# THAT1512_INA128_input_NEVIN_v4.net
KiCad netlist of a schematic drawn in EAGLE
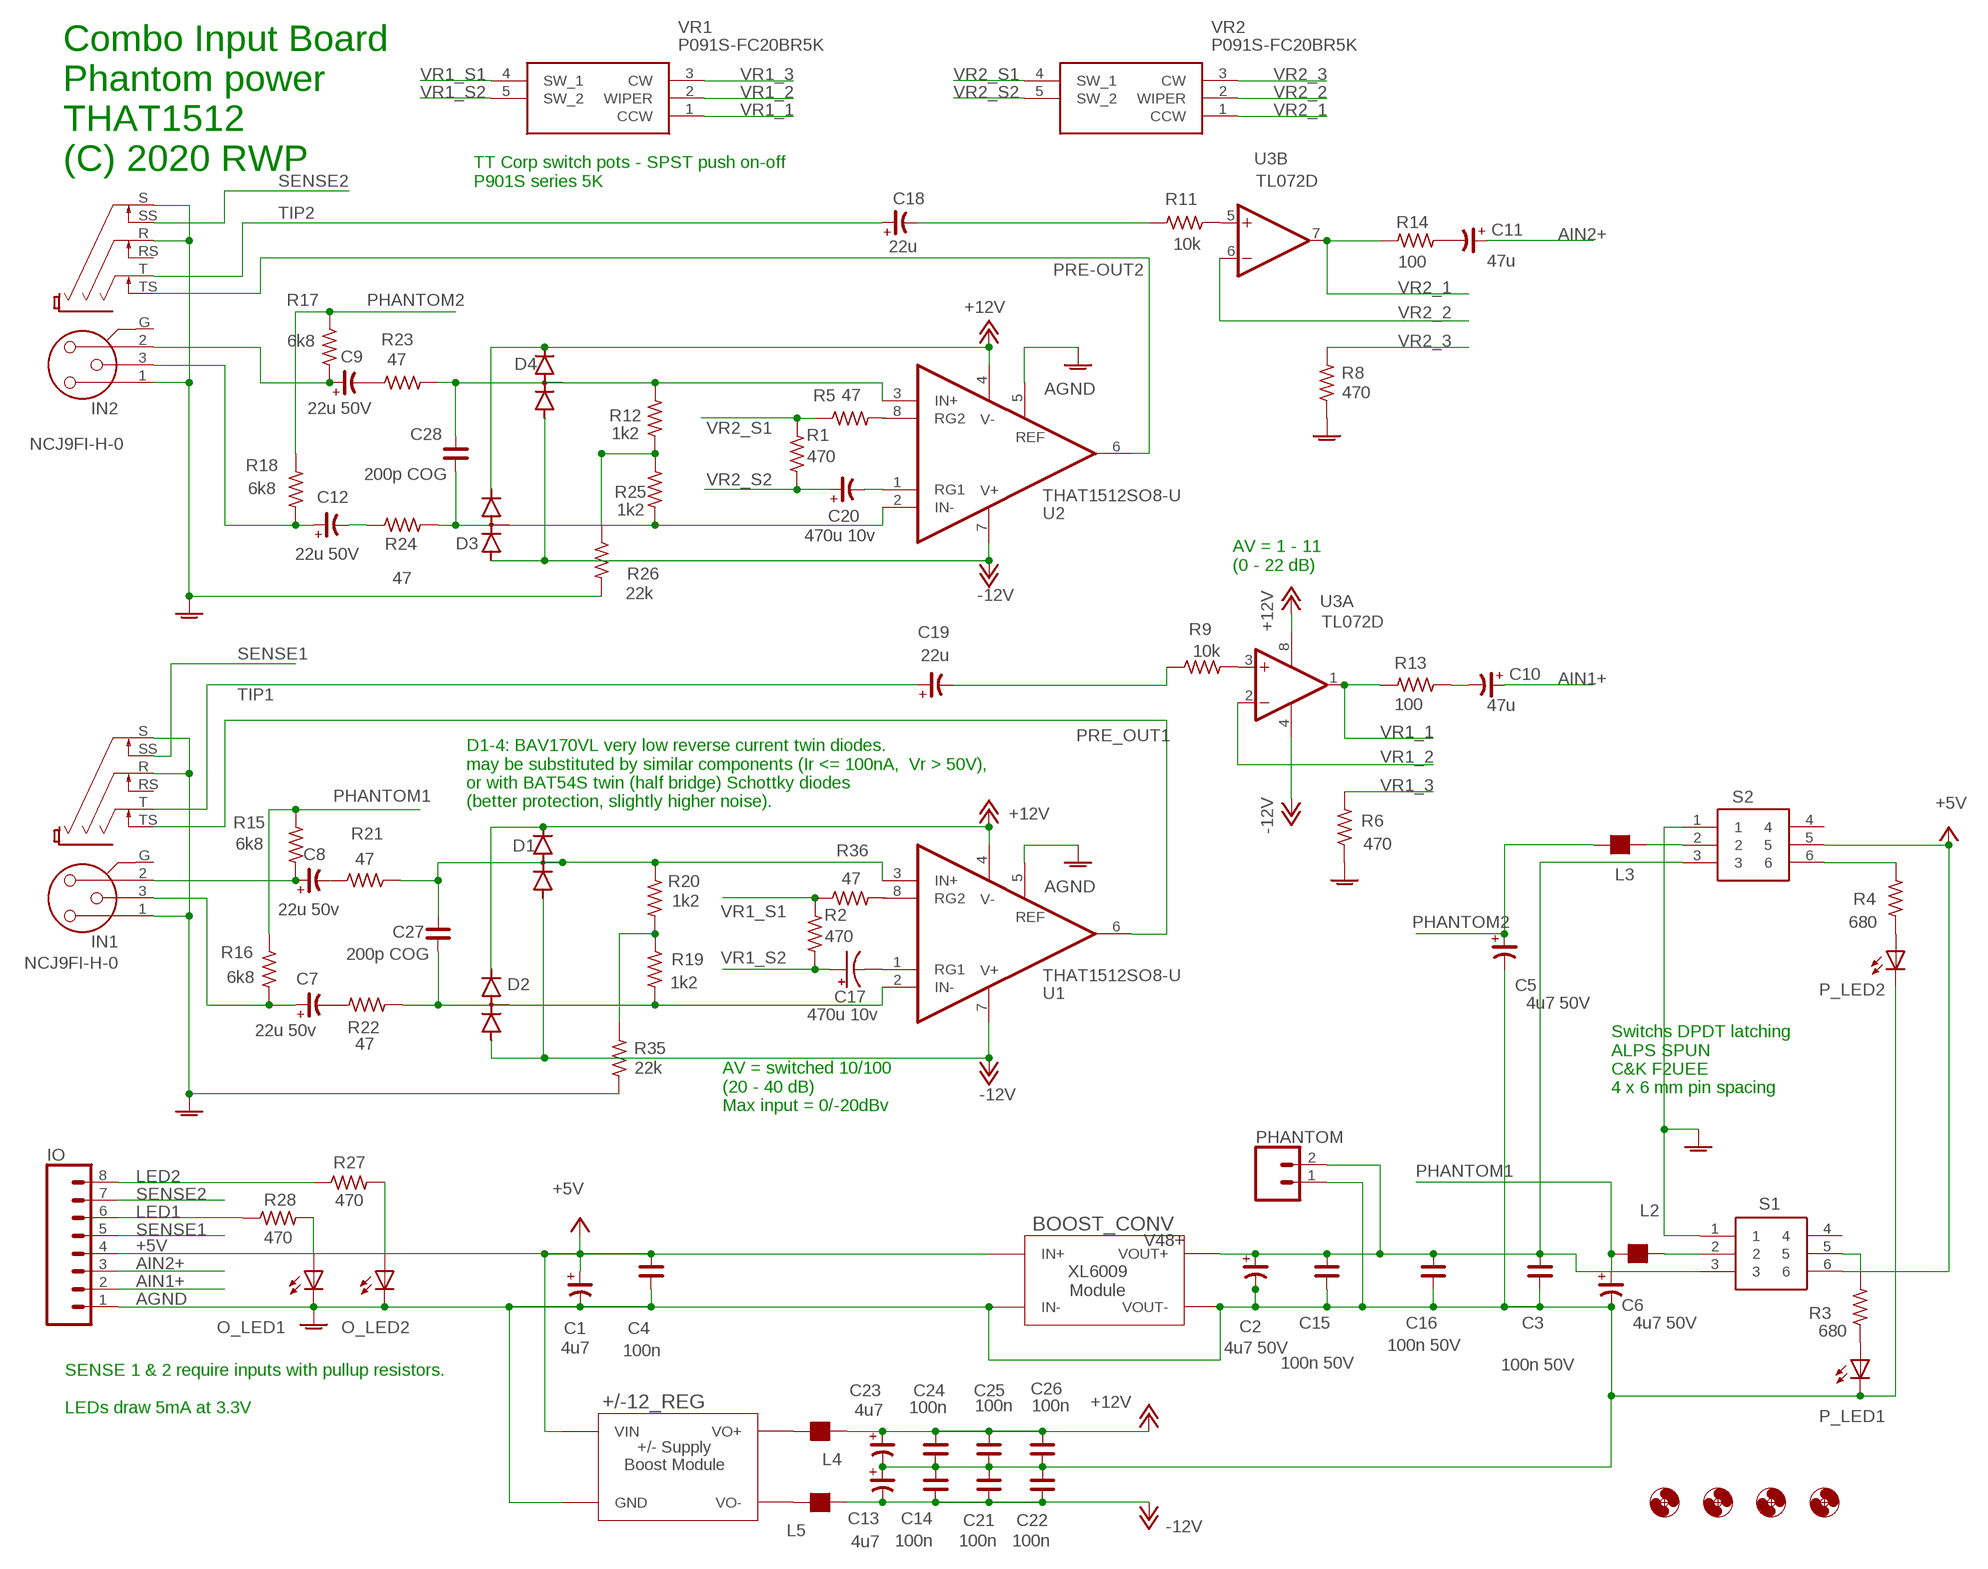
[diagram p0: schematic, sheet 1]

(export (version "E")
  (design (tool "Eeschema 10.0.6"))
  (components
    (comp (ref "+/-12_REG")
      (value "POS_NEG_SUP_MODULE")
      (footprint "eagle-import:POS_NEG_SUP_MODULE_F")
      (libsource (lib "eagle-import") (part "POS_NEG_SUP_MODULE"))
    )
    (comp (ref "BOOST_CONV")
      (value "XL6009_MODULE")
      (footprint "eagle-import:XL6009_MODULE_F")
      (libsource (lib "eagle-import") (part "XL6009_MODULE"))
    )
    (comp (ref "C1")
      (value "4u7")
      (footprint "eagle-import:C3216_T")
      (libsource (lib "eagle-import") (part "CP_3216"))
    )
    (comp (ref "C2")
      (value "4u7 50V")
      (footprint "eagle-import:C3216_T")
      (libsource (lib "eagle-import") (part "CP_3216"))
    )
    (comp (ref "C3")
      (value "100n 50V")
      (footprint "eagle-import:C0805")
      (libsource (lib "eagle-import") (part "C_0805"))
    )
    (comp (ref "C4")
      (value "100n")
      (footprint "eagle-import:C0805")
      (libsource (lib "eagle-import") (part "C_0805"))
    )
    (comp (ref "C5")
      (value "4u7 50V")
      (footprint "eagle-import:C3216_T")
      (libsource (lib "eagle-import") (part "CP_3216"))
    )
    (comp (ref "C6")
      (value "4u7 50V")
      (footprint "eagle-import:C3216_T")
      (libsource (lib "eagle-import") (part "CP_3216"))
    )
    (comp (ref "C7")
      (value "22u 50v")
      (footprint "eagle-import:CSV-C")
      (libsource (lib "eagle-import") (part "CP_SV-C"))
    )
    (comp (ref "C8")
      (value "22u 50v")
      (footprint "eagle-import:CSV-C")
      (libsource (lib "eagle-import") (part "CP_SV-C"))
    )
    (comp (ref "C9")
      (value "22u 50V")
      (footprint "eagle-import:CSV-C")
      (libsource (lib "eagle-import") (part "CP_SV-C"))
    )
    (comp (ref "C10")
      (value "47u")
      (footprint "eagle-import:CSV-B")
      (libsource (lib "eagle-import") (part "CP_SV-B"))
    )
    (comp (ref "C11")
      (value "47u")
      (footprint "eagle-import:CSV-B")
      (libsource (lib "eagle-import") (part "CP_SV-B"))
    )
    (comp (ref "C12")
      (value "22u 50V")
      (footprint "eagle-import:CSV-C")
      (libsource (lib "eagle-import") (part "CP_SV-C"))
    )
    (comp (ref "C13")
      (value "4u7")
      (footprint "eagle-import:C3216_T")
      (libsource (lib "eagle-import") (part "CP_3216"))
    )
    (comp (ref "C14")
      (value "100n")
      (footprint "eagle-import:C0805")
      (libsource (lib "eagle-import") (part "C_0805"))
    )
    (comp (ref "C15")
      (value "100n 50V")
      (footprint "eagle-import:C0805")
      (libsource (lib "eagle-import") (part "C_0805"))
    )
    (comp (ref "C16")
      (value "100n 50V")
      (footprint "eagle-import:C0805")
      (libsource (lib "eagle-import") (part "C_0805"))
    )
    (comp (ref "C17")
      (value "470u 10v")
      (footprint "eagle-import:153CLV-0605")
      (libsource (lib "eagle-import") (part "CPOL-US153CLV-0605"))
    )
    (comp (ref "C18")
      (value "22u")
      (footprint "eagle-import:CSV-B")
      (libsource (lib "eagle-import") (part "CP_SV-B"))
    )
    (comp (ref "C19")
      (value "22u")
      (footprint "eagle-import:CSV-B")
      (libsource (lib "eagle-import") (part "CP_SV-B"))
    )
    (comp (ref "C20")
      (value "470u 10v")
      (footprint "eagle-import:CSV-C")
      (libsource (lib "eagle-import") (part "CP_SV-C"))
    )
    (comp (ref "C21")
      (value "100n")
      (footprint "eagle-import:C0805")
      (libsource (lib "eagle-import") (part "C_0805"))
    )
    (comp (ref "C22")
      (value "100n")
      (footprint "eagle-import:C0805")
      (libsource (lib "eagle-import") (part "C_0805"))
    )
    (comp (ref "C23")
      (value "4u7")
      (footprint "eagle-import:C3216_T")
      (libsource (lib "eagle-import") (part "CP_3216"))
    )
    (comp (ref "C24")
      (value "100n")
      (footprint "eagle-import:C0805")
      (libsource (lib "eagle-import") (part "C_0805"))
    )
    (comp (ref "C25")
      (value "100n")
      (footprint "eagle-import:C0805")
      (libsource (lib "eagle-import") (part "C_0805"))
    )
    (comp (ref "C26")
      (value "100n")
      (footprint "eagle-import:C0805")
      (libsource (lib "eagle-import") (part "C_0805"))
    )
    (comp (ref "C27")
      (value "200p COG")
      (footprint "eagle-import:C0805")
      (libsource (lib "eagle-import") (part "C_0805"))
    )
    (comp (ref "C28")
      (value "200p COG")
      (footprint "eagle-import:C0805")
      (libsource (lib "eagle-import") (part "C_0805"))
    )
    (comp (ref "D1")
      (value "HSMS-285C")
      (footprint "eagle-import:SOT323")
      (libsource (lib "eagle-import") (part "HSMS-285C"))
    )
    (comp (ref "D2")
      (value "HSMS-285C")
      (footprint "eagle-import:SOT323")
      (libsource (lib "eagle-import") (part "HSMS-285C"))
    )
    (comp (ref "D3")
      (value "HSMS-285C")
      (footprint "eagle-import:SOT323")
      (libsource (lib "eagle-import") (part "HSMS-285C"))
    )
    (comp (ref "D4")
      (value "HSMS-285C")
      (footprint "eagle-import:SOT323")
      (libsource (lib "eagle-import") (part "HSMS-285C"))
    )
    (comp (ref "H1")
      (value "MOUNT-HOLE3.6")
      (footprint "eagle-import:3,6")
      (libsource (lib "eagle-import") (part "MOUNT-HOLE3.6"))
    )
    (comp (ref "H2")
      (value "MOUNT-HOLE3.6")
      (footprint "eagle-import:3,6")
      (libsource (lib "eagle-import") (part "MOUNT-HOLE3.6"))
    )
    (comp (ref "H3")
      (value "MOUNT-HOLE3.6")
      (footprint "eagle-import:3,6")
      (libsource (lib "eagle-import") (part "MOUNT-HOLE3.6"))
    )
    (comp (ref "H4")
      (value "MOUNT-HOLE3.6")
      (footprint "eagle-import:3,6")
      (libsource (lib "eagle-import") (part "MOUNT-HOLE3.6"))
    )
    (comp (ref "IN1")
      (value "NCJ9FI-H-0")
      (footprint "eagle-import:NCJ9FI-H")
      (libsource (lib "eagle-import") (part "NCJ9FI-H-0"))
    )
    (comp (ref "IN2")
      (value "NCJ9FI-H-0")
      (footprint "eagle-import:NCJ9FI-H")
      (libsource (lib "eagle-import") (part "NCJ9FI-H-0"))
    )
    (comp (ref "IO")
      (value "CONN_08\"")
      (footprint "eagle-import:1X08")
      (libsource (lib "eagle-import") (part "CONN_08{dblquote}"))
    )
    (comp (ref "L2")
      (value "150")
      (footprint "eagle-import:L0805")
      (libsource (lib "eagle-import") (part "FB_0805"))
    )
    (comp (ref "L3")
      (value "150")
      (footprint "eagle-import:L0805")
      (libsource (lib "eagle-import") (part "FB_0805"))
    )
    (comp (ref "L4")
      (value "150")
      (footprint "eagle-import:L0805")
      (libsource (lib "eagle-import") (part "FB_0805"))
    )
    (comp (ref "L5")
      (value "150")
      (footprint "eagle-import:L0805")
      (libsource (lib "eagle-import") (part "FB_0805"))
    )
    (comp (ref "O_LED1")
      (value "LED3MM")
      (footprint "eagle-import:LED3MM")
      (libsource (lib "eagle-import") (part "LED3MM"))
    )
    (comp (ref "O_LED2")
      (value "LED3MM")
      (footprint "eagle-import:LED3MM")
      (libsource (lib "eagle-import") (part "LED3MM"))
    )
    (comp (ref "PHANTOM")
      (value "CONN_02")
      (footprint "eagle-import:1X02")
      (libsource (lib "eagle-import") (part "CONN_02"))
    )
    (comp (ref "P_LED1")
      (value "LED3MM")
      (footprint "eagle-import:LED3MM")
      (libsource (lib "eagle-import") (part "LED3MM"))
    )
    (comp (ref "P_LED2")
      (value "LED3MM")
      (footprint "eagle-import:LED3MM")
      (libsource (lib "eagle-import") (part "LED3MM"))
    )
    (comp (ref "R1")
      (value "470")
      (footprint "eagle-import:R0805")
      (libsource (lib "eagle-import") (part "R_0805"))
    )
    (comp (ref "R2")
      (value "470")
      (footprint "eagle-import:R0805")
      (libsource (lib "eagle-import") (part "R_0805"))
    )
    (comp (ref "R3")
      (value "680")
      (footprint "eagle-import:R0805")
      (libsource (lib "eagle-import") (part "R_0805"))
    )
    (comp (ref "R4")
      (value "680")
      (footprint "eagle-import:R0805")
      (libsource (lib "eagle-import") (part "R_0805"))
    )
    (comp (ref "R5")
      (value "47")
      (footprint "eagle-import:R0805")
      (libsource (lib "eagle-import") (part "R_0805"))
    )
    (comp (ref "R6")
      (value "470")
      (footprint "eagle-import:R0805")
      (libsource (lib "eagle-import") (part "R_0805"))
    )
    (comp (ref "R8")
      (value "470")
      (footprint "eagle-import:R0805")
      (libsource (lib "eagle-import") (part "R_0805"))
    )
    (comp (ref "R9")
      (value "10k")
      (footprint "eagle-import:R0805")
      (libsource (lib "eagle-import") (part "R_0805"))
    )
    (comp (ref "R11")
      (value "10k")
      (footprint "eagle-import:R0805")
      (libsource (lib "eagle-import") (part "R_0805"))
    )
    (comp (ref "R12")
      (value "1k2")
      (footprint "eagle-import:R0805")
      (libsource (lib "eagle-import") (part "R_0805"))
    )
    (comp (ref "R13")
      (value "100")
      (footprint "eagle-import:R0805")
      (libsource (lib "eagle-import") (part "R_0805"))
    )
    (comp (ref "R14")
      (value "100")
      (footprint "eagle-import:R0805")
      (libsource (lib "eagle-import") (part "R_0805"))
    )
    (comp (ref "R15")
      (value "6k8")
      (footprint "eagle-import:R0805")
      (libsource (lib "eagle-import") (part "R_0805"))
    )
    (comp (ref "R16")
      (value "6k8")
      (footprint "eagle-import:R0805")
      (libsource (lib "eagle-import") (part "R_0805"))
    )
    (comp (ref "R17")
      (value "6k8")
      (footprint "eagle-import:R0805")
      (libsource (lib "eagle-import") (part "R_0805"))
    )
    (comp (ref "R18")
      (value "6k8")
      (footprint "eagle-import:R0805")
      (libsource (lib "eagle-import") (part "R_0805"))
    )
    (comp (ref "R19")
      (value "1k2")
      (footprint "eagle-import:R0805")
      (libsource (lib "eagle-import") (part "R_0805"))
    )
    (comp (ref "R20")
      (value "1k2")
      (footprint "eagle-import:R0805")
      (libsource (lib "eagle-import") (part "R_0805"))
    )
    (comp (ref "R21")
      (value "47")
      (footprint "eagle-import:R0805")
      (libsource (lib "eagle-import") (part "R_0805"))
    )
    (comp (ref "R22")
      (value "47")
      (footprint "eagle-import:R0805")
      (libsource (lib "eagle-import") (part "R_0805"))
    )
    (comp (ref "R23")
      (value "47")
      (footprint "eagle-import:R0805")
      (libsource (lib "eagle-import") (part "R_0805"))
    )
    (comp (ref "R24")
      (value "47")
      (footprint "eagle-import:R0805")
      (libsource (lib "eagle-import") (part "R_0805"))
    )
    (comp (ref "R25")
      (value "1k2")
      (footprint "eagle-import:R0805")
      (libsource (lib "eagle-import") (part "R_0805"))
    )
    (comp (ref "R26")
      (value "22k")
      (footprint "eagle-import:R0805")
      (libsource (lib "eagle-import") (part "R_0805"))
    )
    (comp (ref "R27")
      (value "470")
      (footprint "eagle-import:R0805")
      (libsource (lib "eagle-import") (part "R_0805"))
    )
    (comp (ref "R28")
      (value "470")
      (footprint "eagle-import:R0805")
      (libsource (lib "eagle-import") (part "R_0805"))
    )
    (comp (ref "R35")
      (value "22k")
      (footprint "eagle-import:R0805")
      (libsource (lib "eagle-import") (part "R_0805"))
    )
    (comp (ref "R36")
      (value "47")
      (footprint "eagle-import:R0805")
      (libsource (lib "eagle-import") (part "R_0805"))
    )
    (comp (ref "S1")
      (value "SPUN191600")
      (footprint "eagle-import:SPUN191000")
      (fields (field (name "MOUSER_PART_NUMBER") "688-SPUN191600"))
      (libsource (lib "eagle-import") (part "SPUN191600"))
    )
    (comp (ref "S2")
      (value "SPUN191600")
      (footprint "eagle-import:SPUN191000")
      (fields (field (name "MOUSER_PART_NUMBER") "688-SPUN191600"))
      (libsource (lib "eagle-import") (part "SPUN191600"))
    )
    (comp (ref "U1")
      (value "THAT1512SO8-U")
      (footprint "eagle-import:SO08")
      (libsource (lib "eagle-import") (part "THAT1512SO8-U"))
    )
    (comp (ref "U2")
      (value "THAT1512SO8-U")
      (footprint "eagle-import:SO08")
      (libsource (lib "eagle-import") (part "THAT1512SO8-U"))
    )
    (comp (ref "U3")
      (value "TL072D")
      (footprint "eagle-import:SO08")
      (libsource (lib "eagle-import") (part "TL072D"))
    )
    (comp (ref "VR1")
      (value "P091S-FC20BR5K")
      (footprint "eagle-import:P091SFC20BR5K")
      (fields (field (name "MOUSER_PART_NUMBER") "858-P091SFC20BR5K"))
      (libsource (lib "eagle-import") (part "P091S-FC20BR5K"))
    )
    (comp (ref "VR2")
      (value "P091S-FC20BR5K")
      (footprint "eagle-import:P091SFC20BR5K")
      (fields (field (name "MOUSER_PART_NUMBER") "858-P091SFC20BR5K"))
      (libsource (lib "eagle-import") (part "P091S-FC20BR5K"))
    )
  )
  (nets
    (net (code "1") (name "+5V") (class "Default")
      (node (ref "+/-12_REG") (pin "IN+") (pinfunction "VIN_IN+") (pintype "input"))
      (node (ref "BOOST_CONV") (pin "IN+") (pinfunction "IN+_IN+") (pintype "input"))
      (node (ref "C1") (pin "+") (pinfunction "+_+") (pintype "passive"))
      (node (ref "C4") (pin "2") (pinfunction "2_2") (pintype "passive"))
      (node (ref "IO") (pin "4") (pinfunction "4_4") (pintype "passive"))
      (node (ref "S1") (pin "6") (pinfunction "6_6") (pintype "bidirectional"))
      (node (ref "S2") (pin "5") (pinfunction "5_5") (pintype "bidirectional"))
    )
    (net (code "2") (name "+12V") (class "Default")
      (node (ref "C23") (pin "+") (pinfunction "+_+") (pintype "passive"))
      (node (ref "C24") (pin "2") (pinfunction "2_2") (pintype "passive"))
      (node (ref "C25") (pin "2") (pinfunction "2_2") (pintype "passive"))
      (node (ref "C26") (pin "2") (pinfunction "2_2") (pintype "passive"))
      (node (ref "D1") (pin "2") (pinfunction "C_2") (pintype "passive"))
      (node (ref "D2") (pin "2") (pinfunction "C_2") (pintype "passive"))
      (node (ref "D3") (pin "2") (pinfunction "C_2") (pintype "passive"))
      (node (ref "D4") (pin "2") (pinfunction "C_2") (pintype "passive"))
      (node (ref "L4") (pin "1") (pinfunction "1_1") (pintype "passive"))
      (node (ref "U1") (pin "4") (pinfunction "V-_4") (pintype "power_in"))
      (node (ref "U2") (pin "4") (pinfunction "V-_4") (pintype "power_in"))
      (node (ref "U3") (pin "8") (pinfunction "V+_8") (pintype "power_in"))
    )
    (net (code "3") (name "-12V") (class "Default")
      (node (ref "C13") (pin "-") (pinfunction "-_-") (pintype "passive"))
      (node (ref "C14") (pin "1") (pinfunction "1_1") (pintype "passive"))
      (node (ref "C21") (pin "1") (pinfunction "1_1") (pintype "passive"))
      (node (ref "C22") (pin "1") (pinfunction "1_1") (pintype "passive"))
      (node (ref "D1") (pin "1") (pinfunction "A_1") (pintype "passive"))
      (node (ref "D2") (pin "1") (pinfunction "A_1") (pintype "passive"))
      (node (ref "D3") (pin "1") (pinfunction "A_1") (pintype "passive"))
      (node (ref "D4") (pin "1") (pinfunction "A_1") (pintype "passive"))
      (node (ref "L5") (pin "1") (pinfunction "1_1") (pintype "passive"))
      (node (ref "U1") (pin "7") (pinfunction "V+_7") (pintype "power_in"))
      (node (ref "U2") (pin "7") (pinfunction "V+_7") (pintype "power_in"))
      (node (ref "U3") (pin "4") (pinfunction "V-_4") (pintype "power_in"))
    )
    (net (code "4") (name "/AIN1+") (class "Default")
      (node (ref "C10") (pin "+") (pinfunction "+_+") (pintype "passive"))
      (node (ref "IO") (pin "2") (pinfunction "2_2") (pintype "passive"))
    )
    (net (code "5") (name "/AIN2+") (class "Default")
      (node (ref "C11") (pin "+") (pinfunction "+_+") (pintype "passive"))
      (node (ref "IO") (pin "3") (pinfunction "3_3") (pintype "passive"))
    )
    (net (code "6") (name "/LED1") (class "Default")
      (node (ref "IO") (pin "6") (pinfunction "6_6") (pintype "passive"))
      (node (ref "R28") (pin "2") (pinfunction "2_2") (pintype "passive"))
    )
    (net (code "7") (name "/LED2") (class "Default")
      (node (ref "IO") (pin "8") (pinfunction "8_8") (pintype "passive"))
      (node (ref "R27") (pin "2") (pinfunction "2_2") (pintype "passive"))
    )
    (net (code "8") (name "/PHANTOM1") (class "Default")
      (node (ref "C6") (pin "+") (pinfunction "+_+") (pintype "passive"))
      (node (ref "L2") (pin "2") (pinfunction "2_2") (pintype "passive"))
      (node (ref "R15") (pin "2") (pinfunction "2_2") (pintype "passive"))
      (node (ref "R16") (pin "2") (pinfunction "2_2") (pintype "passive"))
    )
    (net (code "9") (name "/PHANTOM2") (class "Default")
      (node (ref "C5") (pin "+") (pinfunction "+_+") (pintype "passive"))
      (node (ref "L3") (pin "2") (pinfunction "2_2") (pintype "passive"))
      (node (ref "R17") (pin "2") (pinfunction "2_2") (pintype "passive"))
      (node (ref "R18") (pin "2") (pinfunction "2_2") (pintype "passive"))
    )
    (net (code "10") (name "/PRE-OUT2") (class "Default")
      (node (ref "IN2") (pin "TS") (pinfunction "TS_TS") (pintype "passive"))
      (node (ref "U2") (pin "6") (pinfunction "OUT_6") (pintype "output"))
    )
    (net (code "11") (name "/PRE_OUT1") (class "Default")
      (node (ref "IN1") (pin "TS") (pinfunction "TS_TS") (pintype "passive"))
      (node (ref "U1") (pin "6") (pinfunction "OUT_6") (pintype "output"))
    )
    (net (code "12") (name "/SENSE1") (class "Default")
      (node (ref "IN1") (pin "SS") (pinfunction "SS_SS") (pintype "passive"))
      (node (ref "IO") (pin "5") (pinfunction "5_5") (pintype "passive"))
    )
    (net (code "13") (name "/SENSE2") (class "Default")
      (node (ref "IN2") (pin "SS") (pinfunction "SS_SS") (pintype "passive"))
      (node (ref "IO") (pin "7") (pinfunction "7_7") (pintype "passive"))
    )
    (net (code "14") (name "/TIP1") (class "Default")
      (node (ref "C19") (pin "+") (pinfunction "+_+") (pintype "passive"))
      (node (ref "IN1") (pin "T") (pinfunction "T_T") (pintype "passive"))
    )
    (net (code "15") (name "/TIP2") (class "Default")
      (node (ref "C18") (pin "+") (pinfunction "+_+") (pintype "passive"))
      (node (ref "IN2") (pin "T") (pinfunction "T_T") (pintype "passive"))
    )
    (net (code "16") (name "/V48+") (class "Default")
      (node (ref "BOOST_CONV") (pin "VOUT+") (pinfunction "VOUT+_VOUT+") (pintype "output"))
      (node (ref "C15") (pin "2") (pinfunction "2_2") (pintype "passive"))
      (node (ref "C16") (pin "2") (pinfunction "2_2") (pintype "passive"))
      (node (ref "C2") (pin "+") (pinfunction "+_+") (pintype "passive"))
      (node (ref "C3") (pin "2") (pinfunction "2_2") (pintype "passive"))
      (node (ref "PHANTOM") (pin "2") (pinfunction "2_2") (pintype "passive"))
      (node (ref "S1") (pin "3") (pinfunction "3_3") (pintype "bidirectional"))
      (node (ref "S2") (pin "3") (pinfunction "3_3") (pintype "bidirectional"))
    )
    (net (code "17") (name "/VR1_1") (class "Default")
      (node (ref "R13") (pin "2") (pinfunction "2_2") (pintype "passive"))
      (node (ref "U3") (pin "1") (pinfunction "OUT_1") (pintype "output"))
      (node (ref "VR1") (pin "1") (pinfunction "CCW_1") (pintype "bidirectional"))
    )
    (net (code "18") (name "/VR1_2") (class "Default")
      (node (ref "U3") (pin "2") (pinfunction "-IN_2") (pintype "input"))
      (node (ref "VR1") (pin "2") (pinfunction "WIPER_2") (pintype "bidirectional"))
    )
    (net (code "19") (name "/VR1_3") (class "Default")
      (node (ref "R6") (pin "1") (pinfunction "1_1") (pintype "passive"))
      (node (ref "VR1") (pin "3") (pinfunction "CW_3") (pintype "bidirectional"))
    )
    (net (code "20") (name "/VR1_S1") (class "Default")
      (node (ref "R2") (pin "1") (pinfunction "1_1") (pintype "passive"))
      (node (ref "R36") (pin "1") (pinfunction "1_1") (pintype "passive"))
      (node (ref "VR1") (pin "4") (pinfunction "SW_1_4") (pintype "bidirectional"))
    )
    (net (code "21") (name "/VR1_S2") (class "Default")
      (node (ref "C17") (pin "+") (pinfunction "+_+") (pintype "passive"))
      (node (ref "R2") (pin "2") (pinfunction "2_2") (pintype "passive"))
      (node (ref "VR1") (pin "5") (pinfunction "SW_2_5") (pintype "bidirectional"))
    )
    (net (code "22") (name "/VR2_1") (class "Default")
      (node (ref "R14") (pin "2") (pinfunction "2_2") (pintype "passive"))
      (node (ref "U3") (pin "7") (pinfunction "OUT_7") (pintype "output"))
      (node (ref "VR2") (pin "1") (pinfunction "CCW_1") (pintype "bidirectional"))
    )
    (net (code "23") (name "/VR2_2") (class "Default")
      (node (ref "U3") (pin "6") (pinfunction "-IN_6") (pintype "input"))
      (node (ref "VR2") (pin "2") (pinfunction "WIPER_2") (pintype "bidirectional"))
    )
    (net (code "24") (name "/VR2_3") (class "Default")
      (node (ref "R8") (pin "1") (pinfunction "1_1") (pintype "passive"))
      (node (ref "VR2") (pin "3") (pinfunction "CW_3") (pintype "bidirectional"))
    )
    (net (code "25") (name "/VR2_S1") (class "Default")
      (node (ref "R1") (pin "1") (pinfunction "1_1") (pintype "passive"))
      (node (ref "R5") (pin "1") (pinfunction "1_1") (pintype "passive"))
      (node (ref "VR2") (pin "4") (pinfunction "SW_1_4") (pintype "bidirectional"))
    )
    (net (code "26") (name "/VR2_S2") (class "Default")
      (node (ref "C20") (pin "+") (pinfunction "+_+") (pintype "passive"))
      (node (ref "R1") (pin "2") (pinfunction "2_2") (pintype "passive"))
      (node (ref "VR2") (pin "5") (pinfunction "SW_2_5") (pintype "bidirectional"))
    )
    (net (code "27") (name "AGND") (class "Default")
      (node (ref "+/-12_REG") (pin "GND") (pinfunction "GND_GND") (pintype "input"))
      (node (ref "+/-12_REG") (pin "GND@1") (pinfunction "GND_GND@1") (pintype "input"))
      (node (ref "BOOST_CONV") (pin "IN-") (pinfunction "IN-_IN-") (pintype "input"))
      (node (ref "BOOST_CONV") (pin "VOUT-") (pinfunction "VOUT-_VOUT-") (pintype "output"))
      (node (ref "C1") (pin "-") (pinfunction "-_-") (pintype "passive"))
      (node (ref "C13") (pin "+") (pinfunction "+_+") (pintype "passive"))
      (node (ref "C14") (pin "2") (pinfunction "2_2") (pintype "passive"))
      (node (ref "C15") (pin "1") (pinfunction "1_1") (pintype "passive"))
      (node (ref "C16") (pin "1") (pinfunction "1_1") (pintype "passive"))
      (node (ref "C2") (pin "-") (pinfunction "-_-") (pintype "passive"))
      (node (ref "C21") (pin "2") (pinfunction "2_2") (pintype "passive"))
      (node (ref "C22") (pin "2") (pinfunction "2_2") (pintype "passive"))
      (node (ref "C23") (pin "-") (pinfunction "-_-") (pintype "passive"))
      (node (ref "C24") (pin "1") (pinfunction "1_1") (pintype "passive"))
      (node (ref "C25") (pin "1") (pinfunction "1_1") (pintype "passive"))
      (node (ref "C26") (pin "1") (pinfunction "1_1") (pintype "passive"))
      (node (ref "C3") (pin "1") (pinfunction "1_1") (pintype "passive"))
      (node (ref "C4") (pin "1") (pinfunction "1_1") (pintype "passive"))
      (node (ref "C5") (pin "-") (pinfunction "-_-") (pintype "passive"))
      (node (ref "C6") (pin "-") (pinfunction "-_-") (pintype "passive"))
      (node (ref "IN1") (pin "1") (pinfunction "1_1") (pintype "passive"))
      (node (ref "IN1") (pin "R") (pinfunction "R_R") (pintype "passive"))
      (node (ref "IN1") (pin "S") (pinfunction "S_S") (pintype "passive"))
      (node (ref "IN2") (pin "1") (pinfunction "1_1") (pintype "passive"))
      (node (ref "IN2") (pin "R") (pinfunction "R_R") (pintype "passive"))
      (node (ref "IN2") (pin "S") (pinfunction "S_S") (pintype "passive"))
      (node (ref "IO") (pin "1") (pinfunction "1_1") (pintype "passive"))
      (node (ref "O_LED1") (pin "K") (pinfunction "C_K") (pintype "passive"))
      (node (ref "O_LED2") (pin "K") (pinfunction "C_K") (pintype "passive"))
      (node (ref "PHANTOM") (pin "1") (pinfunction "1_1") (pintype "passive"))
      (node (ref "P_LED1") (pin "K") (pinfunction "C_K") (pintype "passive"))
      (node (ref "P_LED2") (pin "K") (pinfunction "C_K") (pintype "passive"))
      (node (ref "R26") (pin "2") (pinfunction "2_2") (pintype "passive"))
      (node (ref "R35") (pin "2") (pinfunction "2_2") (pintype "passive"))
      (node (ref "R6") (pin "2") (pinfunction "2_2") (pintype "passive"))
      (node (ref "R8") (pin "2") (pinfunction "2_2") (pintype "passive"))
      (node (ref "S1") (pin "1") (pinfunction "1_1") (pintype "bidirectional"))
      (node (ref "S2") (pin "1") (pinfunction "1_1") (pintype "bidirectional"))
      (node (ref "U1") (pin "5") (pinfunction "REF_5") (pintype "input"))
      (node (ref "U2") (pin "5") (pinfunction "REF_5") (pintype "input"))
    )
    (net (code "28") (name "Net-(+/-12_REG-PadVO+)") (class "Default")
      (node (ref "+/-12_REG") (pin "VO+") (pinfunction "VO+_VO+") (pintype "output"))
      (node (ref "L4") (pin "2") (pinfunction "2_2") (pintype "passive"))
    )
    (net (code "29") (name "Net-(+/-12_REG-PadVO-)") (class "Default")
      (node (ref "+/-12_REG") (pin "VO-") (pinfunction "VO-_VO-") (pintype "output"))
      (node (ref "L5") (pin "2") (pinfunction "2_2") (pintype "passive"))
    )
    (net (code "30") (name "Net-(C7-Pad+)") (class "Default")
      (node (ref "C7") (pin "+") (pinfunction "+_+") (pintype "passive"))
      (node (ref "IN1") (pin "3") (pinfunction "3_3") (pintype "passive"))
      (node (ref "R16") (pin "1") (pinfunction "1_1") (pintype "passive"))
    )
    (net (code "31") (name "Net-(C7-Pad-)") (class "Default")
      (node (ref "C7") (pin "-") (pinfunction "-_-") (pintype "passive"))
      (node (ref "R22") (pin "2") (pinfunction "2_2") (pintype "passive"))
    )
    (net (code "32") (name "Net-(C8-Pad+)") (class "Default")
      (node (ref "C8") (pin "+") (pinfunction "+_+") (pintype "passive"))
      (node (ref "IN1") (pin "2") (pinfunction "2_2") (pintype "passive"))
      (node (ref "R15") (pin "1") (pinfunction "1_1") (pintype "passive"))
    )
    (net (code "33") (name "Net-(C8-Pad-)") (class "Default")
      (node (ref "C8") (pin "-") (pinfunction "-_-") (pintype "passive"))
      (node (ref "R21") (pin "2") (pinfunction "2_2") (pintype "passive"))
    )
    (net (code "34") (name "Net-(C9-Pad+)") (class "Default")
      (node (ref "C9") (pin "+") (pinfunction "+_+") (pintype "passive"))
      (node (ref "IN2") (pin "2") (pinfunction "2_2") (pintype "passive"))
      (node (ref "R17") (pin "1") (pinfunction "1_1") (pintype "passive"))
    )
    (net (code "35") (name "Net-(C9-Pad-)") (class "Default")
      (node (ref "C9") (pin "-") (pinfunction "-_-") (pintype "passive"))
      (node (ref "R23") (pin "2") (pinfunction "2_2") (pintype "passive"))
    )
    (net (code "36") (name "Net-(C10-Pad-)") (class "Default")
      (node (ref "C10") (pin "-") (pinfunction "-_-") (pintype "passive"))
      (node (ref "R13") (pin "1") (pinfunction "1_1") (pintype "passive"))
    )
    (net (code "37") (name "Net-(C11-Pad-)") (class "Default")
      (node (ref "C11") (pin "-") (pinfunction "-_-") (pintype "passive"))
      (node (ref "R14") (pin "1") (pinfunction "1_1") (pintype "passive"))
    )
    (net (code "38") (name "Net-(C12-Pad+)") (class "Default")
      (node (ref "C12") (pin "+") (pinfunction "+_+") (pintype "passive"))
      (node (ref "IN2") (pin "3") (pinfunction "3_3") (pintype "passive"))
      (node (ref "R18") (pin "1") (pinfunction "1_1") (pintype "passive"))
    )
    (net (code "39") (name "Net-(C12-Pad-)") (class "Default")
      (node (ref "C12") (pin "-") (pinfunction "-_-") (pintype "passive"))
      (node (ref "R24") (pin "2") (pinfunction "2_2") (pintype "passive"))
    )
    (net (code "40") (name "Net-(C18-Pad-)") (class "Default")
      (node (ref "C18") (pin "-") (pinfunction "-_-") (pintype "passive"))
      (node (ref "R11") (pin "2") (pinfunction "2_2") (pintype "passive"))
    )
    (net (code "41") (name "Net-(C19-Pad-)") (class "Default")
      (node (ref "C19") (pin "-") (pinfunction "-_-") (pintype "passive"))
      (node (ref "R9") (pin "2") (pinfunction "2_2") (pintype "passive"))
    )
    (net (code "42") (name "Net-(D1-AC)") (class "Default")
      (node (ref "C27") (pin "2") (pinfunction "2_2") (pintype "passive"))
      (node (ref "D1") (pin "3") (pinfunction "AC_3") (pintype "passive"))
      (node (ref "R20") (pin "1") (pinfunction "1_1") (pintype "passive"))
      (node (ref "R21") (pin "1") (pinfunction "1_1") (pintype "passive"))
      (node (ref "U1") (pin "3") (pinfunction "IN+_3") (pintype "input"))
    )
    (net (code "43") (name "Net-(D2-AC)") (class "Default")
      (node (ref "C27") (pin "1") (pinfunction "1_1") (pintype "passive"))
      (node (ref "D2") (pin "3") (pinfunction "AC_3") (pintype "passive"))
      (node (ref "R19") (pin "2") (pinfunction "2_2") (pintype "passive"))
      (node (ref "R22") (pin "1") (pinfunction "1_1") (pintype "passive"))
      (node (ref "U1") (pin "2") (pinfunction "IN-_2") (pintype "input"))
    )
    (net (code "44") (name "Net-(D3-AC)") (class "Default")
      (node (ref "C28") (pin "1") (pinfunction "1_1") (pintype "passive"))
      (node (ref "D3") (pin "3") (pinfunction "AC_3") (pintype "passive"))
      (node (ref "R24") (pin "1") (pinfunction "1_1") (pintype "passive"))
      (node (ref "R25") (pin "2") (pinfunction "2_2") (pintype "passive"))
      (node (ref "U2") (pin "2") (pinfunction "IN-_2") (pintype "input"))
    )
    (net (code "45") (name "Net-(D4-AC)") (class "Default")
      (node (ref "C28") (pin "2") (pinfunction "2_2") (pintype "passive"))
      (node (ref "D4") (pin "3") (pinfunction "AC_3") (pintype "passive"))
      (node (ref "R12") (pin "1") (pinfunction "1_1") (pintype "passive"))
      (node (ref "R23") (pin "1") (pinfunction "1_1") (pintype "passive"))
      (node (ref "U2") (pin "3") (pinfunction "IN+_3") (pintype "input"))
    )
    (net (code "46") (name "Net-(L2-Pad1)") (class "Default")
      (node (ref "L2") (pin "1") (pinfunction "1_1") (pintype "passive"))
      (node (ref "S1") (pin "2") (pinfunction "2_2") (pintype "bidirectional"))
    )
    (net (code "47") (name "Net-(L3-Pad1)") (class "Default")
      (node (ref "L3") (pin "1") (pinfunction "1_1") (pintype "passive"))
      (node (ref "S2") (pin "2") (pinfunction "2_2") (pintype "bidirectional"))
    )
    (net (code "48") (name "Net-(O_LED1-PadA)") (class "Default")
      (node (ref "O_LED1") (pin "A") (pinfunction "A_A") (pintype "passive"))
      (node (ref "R28") (pin "1") (pinfunction "1_1") (pintype "passive"))
    )
    (net (code "49") (name "Net-(O_LED2-PadA)") (class "Default")
      (node (ref "O_LED2") (pin "A") (pinfunction "A_A") (pintype "passive"))
      (node (ref "R27") (pin "1") (pinfunction "1_1") (pintype "passive"))
    )
    (net (code "50") (name "Net-(P_LED1-PadA)") (class "Default")
      (node (ref "P_LED1") (pin "A") (pinfunction "A_A") (pintype "passive"))
      (node (ref "R3") (pin "1") (pinfunction "1_1") (pintype "passive"))
    )
    (net (code "51") (name "Net-(P_LED2-PadA)") (class "Default")
      (node (ref "P_LED2") (pin "A") (pinfunction "A_A") (pintype "passive"))
      (node (ref "R4") (pin "1") (pinfunction "1_1") (pintype "passive"))
    )
    (net (code "52") (name "Net-(R3-Pad2)") (class "Default")
      (node (ref "R3") (pin "2") (pinfunction "2_2") (pintype "passive"))
      (node (ref "S1") (pin "5") (pinfunction "5_5") (pintype "bidirectional"))
    )
    (net (code "53") (name "Net-(R4-Pad2)") (class "Default")
      (node (ref "R4") (pin "2") (pinfunction "2_2") (pintype "passive"))
      (node (ref "S2") (pin "6") (pinfunction "6_6") (pintype "bidirectional"))
    )
    (net (code "54") (name "Net-(R12-Pad2)") (class "Default")
      (node (ref "R12") (pin "2") (pinfunction "2_2") (pintype "passive"))
      (node (ref "R25") (pin "1") (pinfunction "1_1") (pintype "passive"))
      (node (ref "R26") (pin "1") (pinfunction "1_1") (pintype "passive"))
    )
    (net (code "55") (name "Net-(R19-Pad1)") (class "Default")
      (node (ref "R19") (pin "1") (pinfunction "1_1") (pintype "passive"))
      (node (ref "R20") (pin "2") (pinfunction "2_2") (pintype "passive"))
      (node (ref "R35") (pin "1") (pinfunction "1_1") (pintype "passive"))
    )
    (net (code "56") (name "Net-(U1-RG1)") (class "Default")
      (node (ref "C17") (pin "-") (pinfunction "-_-") (pintype "passive"))
      (node (ref "U1") (pin "1") (pinfunction "RG1_1") (pintype "input"))
    )
    (net (code "57") (name "Net-(U1-RG2)") (class "Default")
      (node (ref "R36") (pin "2") (pinfunction "2_2") (pintype "passive"))
      (node (ref "U1") (pin "8") (pinfunction "RG2_8") (pintype "input"))
    )
    (net (code "58") (name "Net-(U2-RG1)") (class "Default")
      (node (ref "C20") (pin "-") (pinfunction "-_-") (pintype "passive"))
      (node (ref "U2") (pin "1") (pinfunction "RG1_1") (pintype "input"))
    )
    (net (code "59") (name "Net-(U2-RG2)") (class "Default")
      (node (ref "R5") (pin "2") (pinfunction "2_2") (pintype "passive"))
      (node (ref "U2") (pin "8") (pinfunction "RG2_8") (pintype "input"))
    )
    (net (code "60") (name "Net-(U3A-+IN)") (class "Default")
      (node (ref "R9") (pin "1") (pinfunction "1_1") (pintype "passive"))
      (node (ref "U3") (pin "3") (pinfunction "+IN_3") (pintype "input"))
    )
    (net (code "61") (name "Net-(U3B-+IN)") (class "Default")
      (node (ref "R11") (pin "1") (pinfunction "1_1") (pintype "passive"))
      (node (ref "U3") (pin "5") (pinfunction "+IN_5") (pintype "input"))
    )
    (net (code "62") (name "unconnected-(IN1-PadG)") (class "Default")
      (node (ref "IN1") (pin "G") (pinfunction "G_G") (pintype "passive"))
    )
    (net (code "63") (name "unconnected-(IN1-PadRS)") (class "Default")
      (node (ref "IN1") (pin "RS") (pinfunction "RS_RS") (pintype "passive"))
    )
    (net (code "64") (name "unconnected-(IN2-PadG)") (class "Default")
      (node (ref "IN2") (pin "G") (pinfunction "G_G") (pintype "passive"))
    )
    (net (code "65") (name "unconnected-(IN2-PadRS)") (class "Default")
      (node (ref "IN2") (pin "RS") (pinfunction "RS_RS") (pintype "passive"))
    )
    (net (code "66") (name "unconnected-(S1-Pad4)") (class "Default")
      (node (ref "S1") (pin "4") (pinfunction "4_4") (pintype "bidirectional"))
    )
    (net (code "67") (name "unconnected-(S2-Pad4)") (class "Default")
      (node (ref "S2") (pin "4") (pinfunction "4_4") (pintype "bidirectional"))
    )
  )
)
